# IOT_Masterv2_301115_Power.net
KiCad netlist of a schematic drawn in Altium Designer
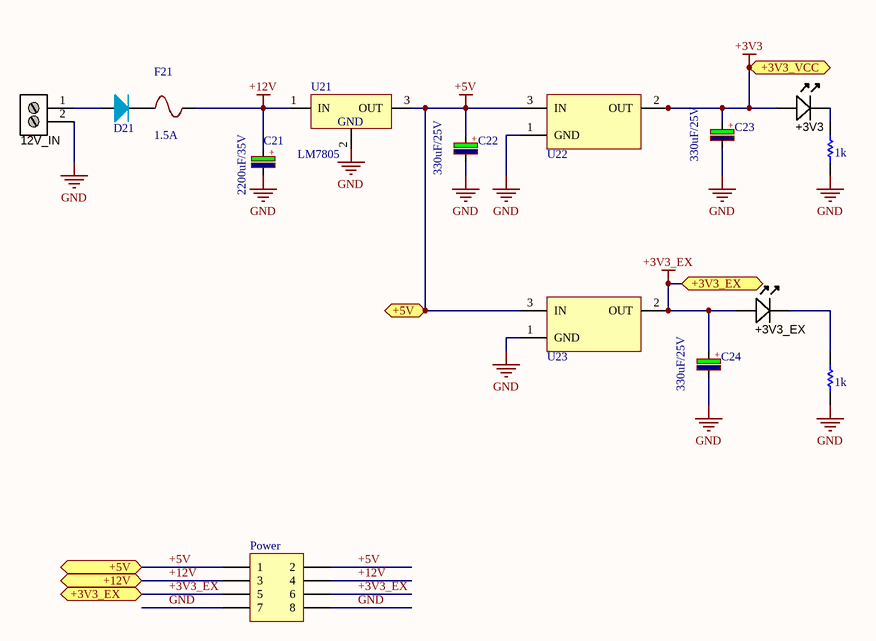
[diagram p0: IOT_Masterv2_301115_Power.SchDoc]

(export (version "E")
  (design (tool "Eeschema 10.0.6"))
  (components
    (comp (ref "+3V3")
      (value "Blue")
      (footprint "LED-0805-K")
      (description "LED 0805 SMD Blue 100mcd 470nm")
      (libsource (lib "PBL - Light Sources") (part "LED_SMD_Blue_0805_100mcd"))
    )
    (comp (ref "+3V3_EX")
      (value "Blue")
      (footprint "LED-0805-K")
      (description "LED 0805 SMD Blue 100mcd 470nm")
      (libsource (lib "PBL - Light Sources") (part "LED_SMD_Blue_0805_100mcd"))
    )
    (comp (ref "12V_IN")
      (value "Stackable ScrewTerm")
      (footprint "2P_PCB_ScrewTerm_200mil")
      (description "Terminal Block Screw Type THT 2-Position 3.81mm pitch")
      (libsource (lib "PBL - Connectors") (part "2P_ScrewTerm_90S_3.81MM"))
    )
    (comp (ref "C21")
      (value "2200uF/35V")
      (footprint "heromap:CP_1000uF_25V")
      (description "Cap 1000uF/16V - 220uF/50V")
      (libsource (lib "heromap") (part "CP4"))
    )
    (comp (ref "C22")
      (value "330uF/25V")
      (footprint "heromap:CP1.5/3.4")
      (description "Cap 1000uF/16V - 220uF/50V")
      (libsource (lib "heromap") (part "CP4"))
    )
    (comp (ref "C23")
      (value "330uF/25V")
      (footprint "heromap:CP1.5/3.4")
      (description "Cap 1000uF/16V - 220uF/50V")
      (libsource (lib "heromap") (part "CP4"))
    )
    (comp (ref "C24")
      (value "330uF/25V")
      (footprint "heromap:CP1.5/3.4")
      (description "Cap 1000uF/16V - 220uF/50V")
      (libsource (lib "heromap") (part "CP4"))
    )
    (comp (ref "D21") (value "Diode") (footprint "DO-214AC") (libsource (lib "Tuan") (part "Diode")))
    (comp (ref "F21") (value "1.5A") (footprint "FUSE_SR-5-BK") (libsource (lib "Tuan") (part "Fuse")))
    (comp (ref "Power")
      (value "Header 4X2")
      (footprint "heromap:HDR2X4")
      (description "Header, 4-Pin, Dual row")
      (fields (field (name "PUBLISHER") "Altium Limited"))
      (libsource (lib "heromap") (part "Header 4X2"))
    )
    (comp (ref "R21")
      (value "1k")
      (footprint "RESC2012N_F")
      (fields (field (name "Comment") "Res_0805_1k"))
      (libsource (lib "Tuan") (part "Res"))
    )
    (comp (ref "R22")
      (value "1k")
      (footprint "RESC2012N_F")
      (fields (field (name "Comment") "Res_0805_1k"))
      (libsource (lib "Tuan") (part "Res"))
    )
    (comp (ref "U21") (value "LM7805") (footprint "TO-220") (libsource (lib "Tuan") (part "LM78xx")))
    (comp (ref "U22") (value "AS1117") (footprint "SOT223-4N") (libsource (lib "Tuan") (part "AS1117")))
    (comp (ref "U23") (value "AS1117") (footprint "SOT223-4N") (libsource (lib "Tuan") (part "AS1117")))
  )
  (nets
    (net (code "1") (name "+3V3") (class "Default")
      (node (ref "+3V3") (pin "A") (pinfunction "A_A") (pintype "passive"))
      (node (ref "C23") (pin "1") (pinfunction "1_1") (pintype "passive"))
      (node (ref "U22") (pin "2") (pinfunction "OUT_2") (pintype "power_in"))
      (node (ref "U22") (pin "4") (pinfunction "4_4") (pintype "passive"))
    )
    (net (code "2") (name "+3V3_EX") (class "Default")
      (node (ref "+3V3_EX") (pin "A") (pinfunction "A_A") (pintype "passive"))
      (node (ref "C24") (pin "1") (pinfunction "1_1") (pintype "passive"))
      (node (ref "Power") (pin "5") (pinfunction "5_5") (pintype "passive"))
      (node (ref "Power") (pin "6") (pinfunction "6_6") (pintype "passive"))
      (node (ref "U23") (pin "2") (pinfunction "OUT_2") (pintype "power_in"))
      (node (ref "U23") (pin "4") (pinfunction "4_4") (pintype "passive"))
    )
    (net (code "3") (name "+5V") (class "Default")
      (node (ref "C22") (pin "1") (pinfunction "1_1") (pintype "passive"))
      (node (ref "Power") (pin "1") (pinfunction "1_1") (pintype "passive"))
      (node (ref "Power") (pin "2") (pinfunction "2_2") (pintype "passive"))
      (node (ref "U21") (pin "3") (pinfunction "OUT_3") (pintype "passive"))
      (node (ref "U22") (pin "3") (pinfunction "IN_3") (pintype "power_in"))
      (node (ref "U23") (pin "3") (pinfunction "IN_3") (pintype "power_in"))
    )
    (net (code "4") (name "+12V") (class "Default")
      (node (ref "C21") (pin "1") (pinfunction "1_1") (pintype "passive"))
      (node (ref "F21") (pin "2") (pinfunction "2_2") (pintype "passive"))
      (node (ref "Power") (pin "3") (pinfunction "3_3") (pintype "passive"))
      (node (ref "Power") (pin "4") (pinfunction "4_4") (pintype "passive"))
      (node (ref "U21") (pin "1") (pinfunction "IN_1") (pintype "passive"))
    )
    (net (code "5") (name "GND") (class "Default")
      (node (ref "12V_IN") (pin "2") (pinfunction "2_2") (pintype "passive"))
      (node (ref "C21") (pin "2") (pinfunction "2_2") (pintype "passive"))
      (node (ref "C22") (pin "2") (pinfunction "2_2") (pintype "passive"))
      (node (ref "C23") (pin "2") (pinfunction "2_2") (pintype "passive"))
      (node (ref "C24") (pin "2") (pinfunction "2_2") (pintype "passive"))
      (node (ref "Power") (pin "7") (pinfunction "7_7") (pintype "passive"))
      (node (ref "Power") (pin "8") (pinfunction "8_8") (pintype "passive"))
      (node (ref "R21") (pin "2") (pinfunction "2_2") (pintype "passive"))
      (node (ref "R22") (pin "2") (pinfunction "2_2") (pintype "passive"))
      (node (ref "U21") (pin "2") (pintype "passive"))
      (node (ref "U22") (pin "1") (pinfunction "GND_1") (pintype "power_in"))
      (node (ref "U23") (pin "1") (pinfunction "GND_1") (pintype "power_in"))
    )
    (net (code "6") (name "Net-(+3V3-PadK)") (class "Default")
      (node (ref "+3V3") (pin "K") (pinfunction "K_K") (pintype "passive"))
      (node (ref "R21") (pin "1") (pinfunction "1_1") (pintype "passive"))
    )
    (net (code "7") (name "Net-(+3V3_EX-PadK)") (class "Default")
      (node (ref "+3V3_EX") (pin "K") (pinfunction "K_K") (pintype "passive"))
      (node (ref "R22") (pin "1") (pinfunction "1_1") (pintype "passive"))
    )
    (net (code "8") (name "Net-(D21-A)") (class "Default")
      (node (ref "12V_IN") (pin "1") (pinfunction "1_1") (pintype "passive"))
      (node (ref "D21") (pin "1") (pinfunction "A_1") (pintype "passive"))
    )
    (net (code "9") (name "Net-(D21-K)") (class "Default")
      (node (ref "D21") (pin "2") (pinfunction "K_2") (pintype "passive"))
      (node (ref "F21") (pin "1") (pinfunction "1_1") (pintype "passive"))
    )
  )
)
